# FPGA_bank34_35.net
KiCad netlist of a schematic drawn in Altium Designer
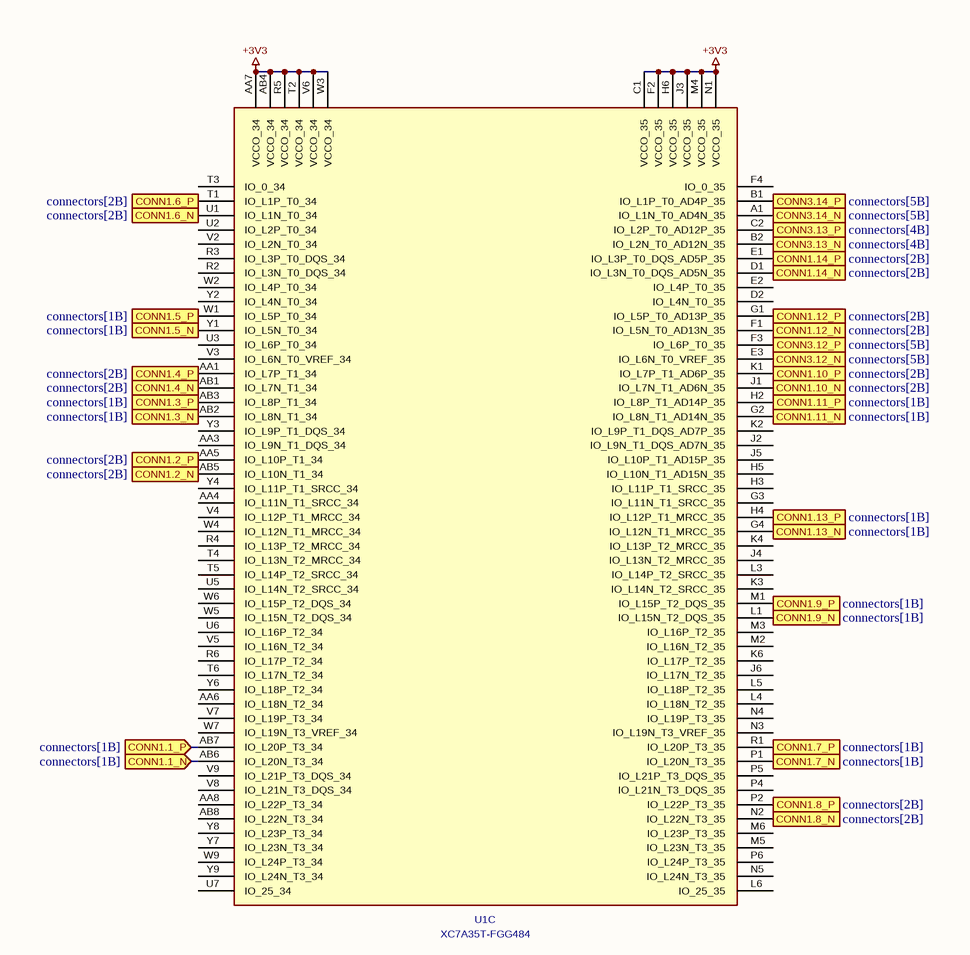
[diagram p0: FPGA_bank34_35.SchDoc]

(export (version "E")
  (design (tool "Eeschema 10.0.6"))
  (components
    (comp (ref "U1")
      (value "XC7A35T-FGG484")
      (footprint "FB-BGA-484_23.0x23.0mm_Layout22x22_P1.0mm")
      (libsource (lib "som_fpga") (part "XC7A35T-FGG484"))
    )
  )
  (nets
    (net (code "1") (name "+3V3") (class "Default")
      (node (ref "U1") (pin "AA7") (pinfunction "VCCO_34_AA7") (pintype "passive"))
      (node (ref "U1") (pin "AB4") (pinfunction "VCCO_34_AB4") (pintype "passive"))
      (node (ref "U1") (pin "C1") (pinfunction "VCCO_35_C1") (pintype "passive"))
      (node (ref "U1") (pin "F2") (pinfunction "VCCO_35_F2") (pintype "passive"))
      (node (ref "U1") (pin "H6") (pinfunction "VCCO_35_H6") (pintype "passive"))
      (node (ref "U1") (pin "J3") (pinfunction "VCCO_35_J3") (pintype "passive"))
      (node (ref "U1") (pin "M4") (pinfunction "VCCO_35_M4") (pintype "passive"))
      (node (ref "U1") (pin "N1") (pinfunction "VCCO_35_N1") (pintype "passive"))
      (node (ref "U1") (pin "R5") (pinfunction "VCCO_34_R5") (pintype "passive"))
      (node (ref "U1") (pin "T2") (pinfunction "VCCO_34_T2") (pintype "passive"))
      (node (ref "U1") (pin "V6") (pinfunction "VCCO_34_V6") (pintype "passive"))
      (node (ref "U1") (pin "W3") (pinfunction "VCCO_34_W3") (pintype "passive"))
    )
    (net (code "2") (name "/CONN1.1_N") (class "Default")
      (node (ref "U1") (pin "AB6") (pinfunction "IO_L20N_T3_34_AB6") (pintype "passive"))
    )
    (net (code "3") (name "/CONN1.1_P") (class "Default")
      (node (ref "U1") (pin "AB7") (pinfunction "IO_L20P_T3_34_AB7") (pintype "passive"))
    )
    (net (code "4") (name "/CONN1.2_N") (class "Default")
      (node (ref "U1") (pin "AB5") (pinfunction "IO_L10N_T1_34_AB5") (pintype "passive"))
    )
    (net (code "5") (name "/CONN1.2_P") (class "Default")
      (node (ref "U1") (pin "AA5") (pinfunction "IO_L10P_T1_34_AA5") (pintype "passive"))
    )
    (net (code "6") (name "/CONN1.3_N") (class "Default")
      (node (ref "U1") (pin "AB2") (pinfunction "IO_L8N_T1_34_AB2") (pintype "passive"))
    )
    (net (code "7") (name "/CONN1.3_P") (class "Default")
      (node (ref "U1") (pin "AB3") (pinfunction "IO_L8P_T1_34_AB3") (pintype "passive"))
    )
    (net (code "8") (name "/CONN1.4_N") (class "Default")
      (node (ref "U1") (pin "AB1") (pinfunction "IO_L7N_T1_34_AB1") (pintype "passive"))
    )
    (net (code "9") (name "/CONN1.4_P") (class "Default")
      (node (ref "U1") (pin "AA1") (pinfunction "IO_L7P_T1_34_AA1") (pintype "passive"))
    )
    (net (code "10") (name "/CONN1.5_N") (class "Default")
      (node (ref "U1") (pin "Y1") (pinfunction "IO_L5N_T0_34_Y1") (pintype "passive"))
    )
    (net (code "11") (name "/CONN1.5_P") (class "Default")
      (node (ref "U1") (pin "W1") (pinfunction "IO_L5P_T0_34_W1") (pintype "passive"))
    )
    (net (code "12") (name "/CONN1.6_N") (class "Default")
      (node (ref "U1") (pin "U1") (pinfunction "IO_L1N_T0_34_U1") (pintype "passive"))
    )
    (net (code "13") (name "/CONN1.6_P") (class "Default")
      (node (ref "U1") (pin "T1") (pinfunction "IO_L1P_T0_34_T1") (pintype "passive"))
    )
    (net (code "14") (name "/CONN1.7_N") (class "Default")
      (node (ref "U1") (pin "P1") (pinfunction "IO_L20N_T3_35_P1") (pintype "passive"))
    )
    (net (code "15") (name "/CONN1.7_P") (class "Default")
      (node (ref "U1") (pin "R1") (pinfunction "IO_L20P_T3_35_R1") (pintype "passive"))
    )
    (net (code "16") (name "/CONN1.8_N") (class "Default")
      (node (ref "U1") (pin "N2") (pinfunction "IO_L22N_T3_35_N2") (pintype "passive"))
    )
    (net (code "17") (name "/CONN1.8_P") (class "Default")
      (node (ref "U1") (pin "P2") (pinfunction "IO_L22P_T3_35_P2") (pintype "passive"))
    )
    (net (code "18") (name "/CONN1.9_N") (class "Default")
      (node (ref "U1") (pin "L1") (pinfunction "IO_L15N_T2_DQS_35_L1") (pintype "passive"))
    )
    (net (code "19") (name "/CONN1.9_P") (class "Default")
      (node (ref "U1") (pin "M1") (pinfunction "IO_L15P_T2_DQS_35_M1") (pintype "passive"))
    )
    (net (code "20") (name "/CONN1.10_N") (class "Default")
      (node (ref "U1") (pin "J1") (pinfunction "IO_L7N_T1_AD6N_35_J1") (pintype "passive"))
    )
    (net (code "21") (name "/CONN1.10_P") (class "Default")
      (node (ref "U1") (pin "K1") (pinfunction "IO_L7P_T1_AD6P_35_K1") (pintype "passive"))
    )
    (net (code "22") (name "/CONN1.11_N") (class "Default")
      (node (ref "U1") (pin "G2") (pinfunction "IO_L8N_T1_AD14N_35_G2") (pintype "passive"))
    )
    (net (code "23") (name "/CONN1.11_P") (class "Default")
      (node (ref "U1") (pin "H2") (pinfunction "IO_L8P_T1_AD14P_35_H2") (pintype "passive"))
    )
    (net (code "24") (name "/CONN1.12_N") (class "Default")
      (node (ref "U1") (pin "F1") (pinfunction "IO_L5N_T0_AD13N_35_F1") (pintype "passive"))
    )
    (net (code "25") (name "/CONN1.12_P") (class "Default")
      (node (ref "U1") (pin "G1") (pinfunction "IO_L5P_T0_AD13P_35_G1") (pintype "passive"))
    )
    (net (code "26") (name "/CONN1.13_N") (class "Default")
      (node (ref "U1") (pin "G4") (pinfunction "IO_L12N_T1_MRCC_35_G4") (pintype "passive"))
    )
    (net (code "27") (name "/CONN1.13_P") (class "Default")
      (node (ref "U1") (pin "H4") (pinfunction "IO_L12P_T1_MRCC_35_H4") (pintype "passive"))
    )
    (net (code "28") (name "/CONN1.14_N") (class "Default")
      (node (ref "U1") (pin "D1") (pinfunction "IO_L3N_T0_DQS_AD5N_35_D1") (pintype "passive"))
    )
    (net (code "29") (name "/CONN1.14_P") (class "Default")
      (node (ref "U1") (pin "E1") (pinfunction "IO_L3P_T0_DQS_AD5P_35_E1") (pintype "passive"))
    )
    (net (code "30") (name "/CONN3.12_N") (class "Default")
      (node (ref "U1") (pin "E3") (pinfunction "IO_L6N_T0_VREF_35_E3") (pintype "passive"))
    )
    (net (code "31") (name "/CONN3.12_P") (class "Default")
      (node (ref "U1") (pin "F3") (pinfunction "IO_L6P_T0_35_F3") (pintype "passive"))
    )
    (net (code "32") (name "/CONN3.13_N") (class "Default")
      (node (ref "U1") (pin "B2") (pinfunction "IO_L2N_T0_AD12N_35_B2") (pintype "passive"))
    )
    (net (code "33") (name "/CONN3.13_P") (class "Default")
      (node (ref "U1") (pin "C2") (pinfunction "IO_L2P_T0_AD12P_35_C2") (pintype "passive"))
    )
    (net (code "34") (name "/CONN3.14_N") (class "Default")
      (node (ref "U1") (pin "A1") (pinfunction "IO_L1N_T0_AD4N_35_A1") (pintype "passive"))
    )
    (net (code "35") (name "/CONN3.14_P") (class "Default")
      (node (ref "U1") (pin "B1") (pinfunction "IO_L1P_T0_AD4P_35_B1") (pintype "passive"))
    )
    (net (code "36") (name "unconnected-(U1C-IO_0_34-PadT3)") (class "Default")
      (node (ref "U1") (pin "T3") (pinfunction "IO_0_34_T3") (pintype "passive"))
    )
    (net (code "37") (name "unconnected-(U1C-IO_0_35-PadF4)") (class "Default")
      (node (ref "U1") (pin "F4") (pinfunction "IO_0_35_F4") (pintype "passive"))
    )
    (net (code "38") (name "unconnected-(U1C-IO_25_34-PadU7)") (class "Default")
      (node (ref "U1") (pin "U7") (pinfunction "IO_25_34_U7") (pintype "passive"))
    )
    (net (code "39") (name "unconnected-(U1C-IO_25_35-PadL6)") (class "Default")
      (node (ref "U1") (pin "L6") (pinfunction "IO_25_35_L6") (pintype "passive"))
    )
    (net (code "40") (name "unconnected-(U1C-IO_L2N_T0_34-PadV2)") (class "Default")
      (node (ref "U1") (pin "V2") (pinfunction "IO_L2N_T0_34_V2") (pintype "passive"))
    )
    (net (code "41") (name "unconnected-(U1C-IO_L2P_T0_34-PadU2)") (class "Default")
      (node (ref "U1") (pin "U2") (pinfunction "IO_L2P_T0_34_U2") (pintype "passive"))
    )
    (net (code "42") (name "unconnected-(U1C-IO_L3N_T0_DQS_34-PadR2)") (class "Default")
      (node (ref "U1") (pin "R2") (pinfunction "IO_L3N_T0_DQS_34_R2") (pintype "passive"))
    )
    (net (code "43") (name "unconnected-(U1C-IO_L3P_T0_DQS_34-PadR3)") (class "Default")
      (node (ref "U1") (pin "R3") (pinfunction "IO_L3P_T0_DQS_34_R3") (pintype "passive"))
    )
    (net (code "44") (name "unconnected-(U1C-IO_L4N_T0_34-PadY2)") (class "Default")
      (node (ref "U1") (pin "Y2") (pinfunction "IO_L4N_T0_34_Y2") (pintype "passive"))
    )
    (net (code "45") (name "unconnected-(U1C-IO_L4N_T0_35-PadD2)") (class "Default")
      (node (ref "U1") (pin "D2") (pinfunction "IO_L4N_T0_35_D2") (pintype "passive"))
    )
    (net (code "46") (name "unconnected-(U1C-IO_L4P_T0_34-PadW2)") (class "Default")
      (node (ref "U1") (pin "W2") (pinfunction "IO_L4P_T0_34_W2") (pintype "passive"))
    )
    (net (code "47") (name "unconnected-(U1C-IO_L4P_T0_35-PadE2)") (class "Default")
      (node (ref "U1") (pin "E2") (pinfunction "IO_L4P_T0_35_E2") (pintype "passive"))
    )
    (net (code "48") (name "unconnected-(U1C-IO_L6N_T0_VREF_34-PadV3)") (class "Default")
      (node (ref "U1") (pin "V3") (pinfunction "IO_L6N_T0_VREF_34_V3") (pintype "passive"))
    )
    (net (code "49") (name "unconnected-(U1C-IO_L6P_T0_34-PadU3)") (class "Default")
      (node (ref "U1") (pin "U3") (pinfunction "IO_L6P_T0_34_U3") (pintype "passive"))
    )
    (net (code "50") (name "unconnected-(U1C-IO_L9N_T1_DQS_34-PadAA3)") (class "Default")
      (node (ref "U1") (pin "AA3") (pinfunction "IO_L9N_T1_DQS_34_AA3") (pintype "passive"))
    )
    (net (code "51") (name "unconnected-(U1C-IO_L9N_T1_DQS_AD7N_35-PadJ2)") (class "Default")
      (node (ref "U1") (pin "J2") (pinfunction "IO_L9N_T1_DQS_AD7N_35_J2") (pintype "passive"))
    )
    (net (code "52") (name "unconnected-(U1C-IO_L9P_T1_DQS_34-PadY3)") (class "Default")
      (node (ref "U1") (pin "Y3") (pinfunction "IO_L9P_T1_DQS_34_Y3") (pintype "passive"))
    )
    (net (code "53") (name "unconnected-(U1C-IO_L9P_T1_DQS_AD7P_35-PadK2)") (class "Default")
      (node (ref "U1") (pin "K2") (pinfunction "IO_L9P_T1_DQS_AD7P_35_K2") (pintype "passive"))
    )
    (net (code "54") (name "unconnected-(U1C-IO_L10N_T1_AD15N_35-PadH5)") (class "Default")
      (node (ref "U1") (pin "H5") (pinfunction "IO_L10N_T1_AD15N_35_H5") (pintype "passive"))
    )
    (net (code "55") (name "unconnected-(U1C-IO_L10P_T1_AD15P_35-PadJ5)") (class "Default")
      (node (ref "U1") (pin "J5") (pinfunction "IO_L10P_T1_AD15P_35_J5") (pintype "passive"))
    )
    (net (code "56") (name "unconnected-(U1C-IO_L11N_T1_SRCC_34-PadAA4)") (class "Default")
      (node (ref "U1") (pin "AA4") (pinfunction "IO_L11N_T1_SRCC_34_AA4") (pintype "passive"))
    )
    (net (code "57") (name "unconnected-(U1C-IO_L11N_T1_SRCC_35-PadG3)") (class "Default")
      (node (ref "U1") (pin "G3") (pinfunction "IO_L11N_T1_SRCC_35_G3") (pintype "passive"))
    )
    (net (code "58") (name "unconnected-(U1C-IO_L11P_T1_SRCC_34-PadY4)") (class "Default")
      (node (ref "U1") (pin "Y4") (pinfunction "IO_L11P_T1_SRCC_34_Y4") (pintype "passive"))
    )
    (net (code "59") (name "unconnected-(U1C-IO_L11P_T1_SRCC_35-PadH3)") (class "Default")
      (node (ref "U1") (pin "H3") (pinfunction "IO_L11P_T1_SRCC_35_H3") (pintype "passive"))
    )
    (net (code "60") (name "unconnected-(U1C-IO_L12N_T1_MRCC_34-PadW4)") (class "Default")
      (node (ref "U1") (pin "W4") (pinfunction "IO_L12N_T1_MRCC_34_W4") (pintype "passive"))
    )
    (net (code "61") (name "unconnected-(U1C-IO_L12P_T1_MRCC_34-PadV4)") (class "Default")
      (node (ref "U1") (pin "V4") (pinfunction "IO_L12P_T1_MRCC_34_V4") (pintype "passive"))
    )
    (net (code "62") (name "unconnected-(U1C-IO_L13N_T2_MRCC_34-PadT4)") (class "Default")
      (node (ref "U1") (pin "T4") (pinfunction "IO_L13N_T2_MRCC_34_T4") (pintype "passive"))
    )
    (net (code "63") (name "unconnected-(U1C-IO_L13N_T2_MRCC_35-PadJ4)") (class "Default")
      (node (ref "U1") (pin "J4") (pinfunction "IO_L13N_T2_MRCC_35_J4") (pintype "passive"))
    )
    (net (code "64") (name "unconnected-(U1C-IO_L13P_T2_MRCC_34-PadR4)") (class "Default")
      (node (ref "U1") (pin "R4") (pinfunction "IO_L13P_T2_MRCC_34_R4") (pintype "passive"))
    )
    (net (code "65") (name "unconnected-(U1C-IO_L13P_T2_MRCC_35-PadK4)") (class "Default")
      (node (ref "U1") (pin "K4") (pinfunction "IO_L13P_T2_MRCC_35_K4") (pintype "passive"))
    )
    (net (code "66") (name "unconnected-(U1C-IO_L14N_T2_SRCC_34-PadU5)") (class "Default")
      (node (ref "U1") (pin "U5") (pinfunction "IO_L14N_T2_SRCC_34_U5") (pintype "passive"))
    )
    (net (code "67") (name "unconnected-(U1C-IO_L14N_T2_SRCC_35-PadK3)") (class "Default")
      (node (ref "U1") (pin "K3") (pinfunction "IO_L14N_T2_SRCC_35_K3") (pintype "passive"))
    )
    (net (code "68") (name "unconnected-(U1C-IO_L14P_T2_SRCC_34-PadT5)") (class "Default")
      (node (ref "U1") (pin "T5") (pinfunction "IO_L14P_T2_SRCC_34_T5") (pintype "passive"))
    )
    (net (code "69") (name "unconnected-(U1C-IO_L14P_T2_SRCC_35-PadL3)") (class "Default")
      (node (ref "U1") (pin "L3") (pinfunction "IO_L14P_T2_SRCC_35_L3") (pintype "passive"))
    )
    (net (code "70") (name "unconnected-(U1C-IO_L15N_T2_DQS_34-PadW5)") (class "Default")
      (node (ref "U1") (pin "W5") (pinfunction "IO_L15N_T2_DQS_34_W5") (pintype "passive"))
    )
    (net (code "71") (name "unconnected-(U1C-IO_L15P_T2_DQS_34-PadW6)") (class "Default")
      (node (ref "U1") (pin "W6") (pinfunction "IO_L15P_T2_DQS_34_W6") (pintype "passive"))
    )
    (net (code "72") (name "unconnected-(U1C-IO_L16N_T2_34-PadV5)") (class "Default")
      (node (ref "U1") (pin "V5") (pinfunction "IO_L16N_T2_34_V5") (pintype "passive"))
    )
    (net (code "73") (name "unconnected-(U1C-IO_L16N_T2_35-PadM2)") (class "Default")
      (node (ref "U1") (pin "M2") (pinfunction "IO_L16N_T2_35_M2") (pintype "passive"))
    )
    (net (code "74") (name "unconnected-(U1C-IO_L16P_T2_34-PadU6)") (class "Default")
      (node (ref "U1") (pin "U6") (pinfunction "IO_L16P_T2_34_U6") (pintype "passive"))
    )
    (net (code "75") (name "unconnected-(U1C-IO_L16P_T2_35-PadM3)") (class "Default")
      (node (ref "U1") (pin "M3") (pinfunction "IO_L16P_T2_35_M3") (pintype "passive"))
    )
    (net (code "76") (name "unconnected-(U1C-IO_L17N_T2_34-PadT6)") (class "Default")
      (node (ref "U1") (pin "T6") (pinfunction "IO_L17N_T2_34_T6") (pintype "passive"))
    )
    (net (code "77") (name "unconnected-(U1C-IO_L17N_T2_35-PadJ6)") (class "Default")
      (node (ref "U1") (pin "J6") (pinfunction "IO_L17N_T2_35_J6") (pintype "passive"))
    )
    (net (code "78") (name "unconnected-(U1C-IO_L17P_T2_34-PadR6)") (class "Default")
      (node (ref "U1") (pin "R6") (pinfunction "IO_L17P_T2_34_R6") (pintype "passive"))
    )
    (net (code "79") (name "unconnected-(U1C-IO_L17P_T2_35-PadK6)") (class "Default")
      (node (ref "U1") (pin "K6") (pinfunction "IO_L17P_T2_35_K6") (pintype "passive"))
    )
    (net (code "80") (name "unconnected-(U1C-IO_L18N_T2_34-PadAA6)") (class "Default")
      (node (ref "U1") (pin "AA6") (pinfunction "IO_L18N_T2_34_AA6") (pintype "passive"))
    )
    (net (code "81") (name "unconnected-(U1C-IO_L18N_T2_35-PadL4)") (class "Default")
      (node (ref "U1") (pin "L4") (pinfunction "IO_L18N_T2_35_L4") (pintype "passive"))
    )
    (net (code "82") (name "unconnected-(U1C-IO_L18P_T2_34-PadY6)") (class "Default")
      (node (ref "U1") (pin "Y6") (pinfunction "IO_L18P_T2_34_Y6") (pintype "passive"))
    )
    (net (code "83") (name "unconnected-(U1C-IO_L18P_T2_35-PadL5)") (class "Default")
      (node (ref "U1") (pin "L5") (pinfunction "IO_L18P_T2_35_L5") (pintype "passive"))
    )
    (net (code "84") (name "unconnected-(U1C-IO_L19N_T3_VREF_34-PadW7)") (class "Default")
      (node (ref "U1") (pin "W7") (pinfunction "IO_L19N_T3_VREF_34_W7") (pintype "passive"))
    )
    (net (code "85") (name "unconnected-(U1C-IO_L19N_T3_VREF_35-PadN3)") (class "Default")
      (node (ref "U1") (pin "N3") (pinfunction "IO_L19N_T3_VREF_35_N3") (pintype "passive"))
    )
    (net (code "86") (name "unconnected-(U1C-IO_L19P_T3_34-PadV7)") (class "Default")
      (node (ref "U1") (pin "V7") (pinfunction "IO_L19P_T3_34_V7") (pintype "passive"))
    )
    (net (code "87") (name "unconnected-(U1C-IO_L19P_T3_35-PadN4)") (class "Default")
      (node (ref "U1") (pin "N4") (pinfunction "IO_L19P_T3_35_N4") (pintype "passive"))
    )
    (net (code "88") (name "unconnected-(U1C-IO_L21N_T3_DQS_34-PadV8)") (class "Default")
      (node (ref "U1") (pin "V8") (pinfunction "IO_L21N_T3_DQS_34_V8") (pintype "passive"))
    )
    (net (code "89") (name "unconnected-(U1C-IO_L21N_T3_DQS_35-PadP4)") (class "Default")
      (node (ref "U1") (pin "P4") (pinfunction "IO_L21N_T3_DQS_35_P4") (pintype "passive"))
    )
    (net (code "90") (name "unconnected-(U1C-IO_L21P_T3_DQS_34-PadV9)") (class "Default")
      (node (ref "U1") (pin "V9") (pinfunction "IO_L21P_T3_DQS_34_V9") (pintype "passive"))
    )
    (net (code "91") (name "unconnected-(U1C-IO_L21P_T3_DQS_35-PadP5)") (class "Default")
      (node (ref "U1") (pin "P5") (pinfunction "IO_L21P_T3_DQS_35_P5") (pintype "passive"))
    )
    (net (code "92") (name "unconnected-(U1C-IO_L22N_T3_34-PadAB8)") (class "Default")
      (node (ref "U1") (pin "AB8") (pinfunction "IO_L22N_T3_34_AB8") (pintype "passive"))
    )
    (net (code "93") (name "unconnected-(U1C-IO_L22P_T3_34-PadAA8)") (class "Default")
      (node (ref "U1") (pin "AA8") (pinfunction "IO_L22P_T3_34_AA8") (pintype "passive"))
    )
    (net (code "94") (name "unconnected-(U1C-IO_L23N_T3_34-PadY7)") (class "Default")
      (node (ref "U1") (pin "Y7") (pinfunction "IO_L23N_T3_34_Y7") (pintype "passive"))
    )
    (net (code "95") (name "unconnected-(U1C-IO_L23N_T3_35-PadM5)") (class "Default")
      (node (ref "U1") (pin "M5") (pinfunction "IO_L23N_T3_35_M5") (pintype "passive"))
    )
    (net (code "96") (name "unconnected-(U1C-IO_L23P_T3_34-PadY8)") (class "Default")
      (node (ref "U1") (pin "Y8") (pinfunction "IO_L23P_T3_34_Y8") (pintype "passive"))
    )
    (net (code "97") (name "unconnected-(U1C-IO_L23P_T3_35-PadM6)") (class "Default")
      (node (ref "U1") (pin "M6") (pinfunction "IO_L23P_T3_35_M6") (pintype "passive"))
    )
    (net (code "98") (name "unconnected-(U1C-IO_L24N_T3_34-PadY9)") (class "Default")
      (node (ref "U1") (pin "Y9") (pinfunction "IO_L24N_T3_34_Y9") (pintype "passive"))
    )
    (net (code "99") (name "unconnected-(U1C-IO_L24N_T3_35-PadN5)") (class "Default")
      (node (ref "U1") (pin "N5") (pinfunction "IO_L24N_T3_35_N5") (pintype "passive"))
    )
    (net (code "100") (name "unconnected-(U1C-IO_L24P_T3_34-PadW9)") (class "Default")
      (node (ref "U1") (pin "W9") (pinfunction "IO_L24P_T3_34_W9") (pintype "passive"))
    )
    (net (code "101") (name "unconnected-(U1C-IO_L24P_T3_35-PadP6)") (class "Default")
      (node (ref "U1") (pin "P6") (pinfunction "IO_L24P_T3_35_P6") (pintype "passive"))
    )
  )
)
